# USB.net
KiCad netlist of a schematic drawn in Altium Designer
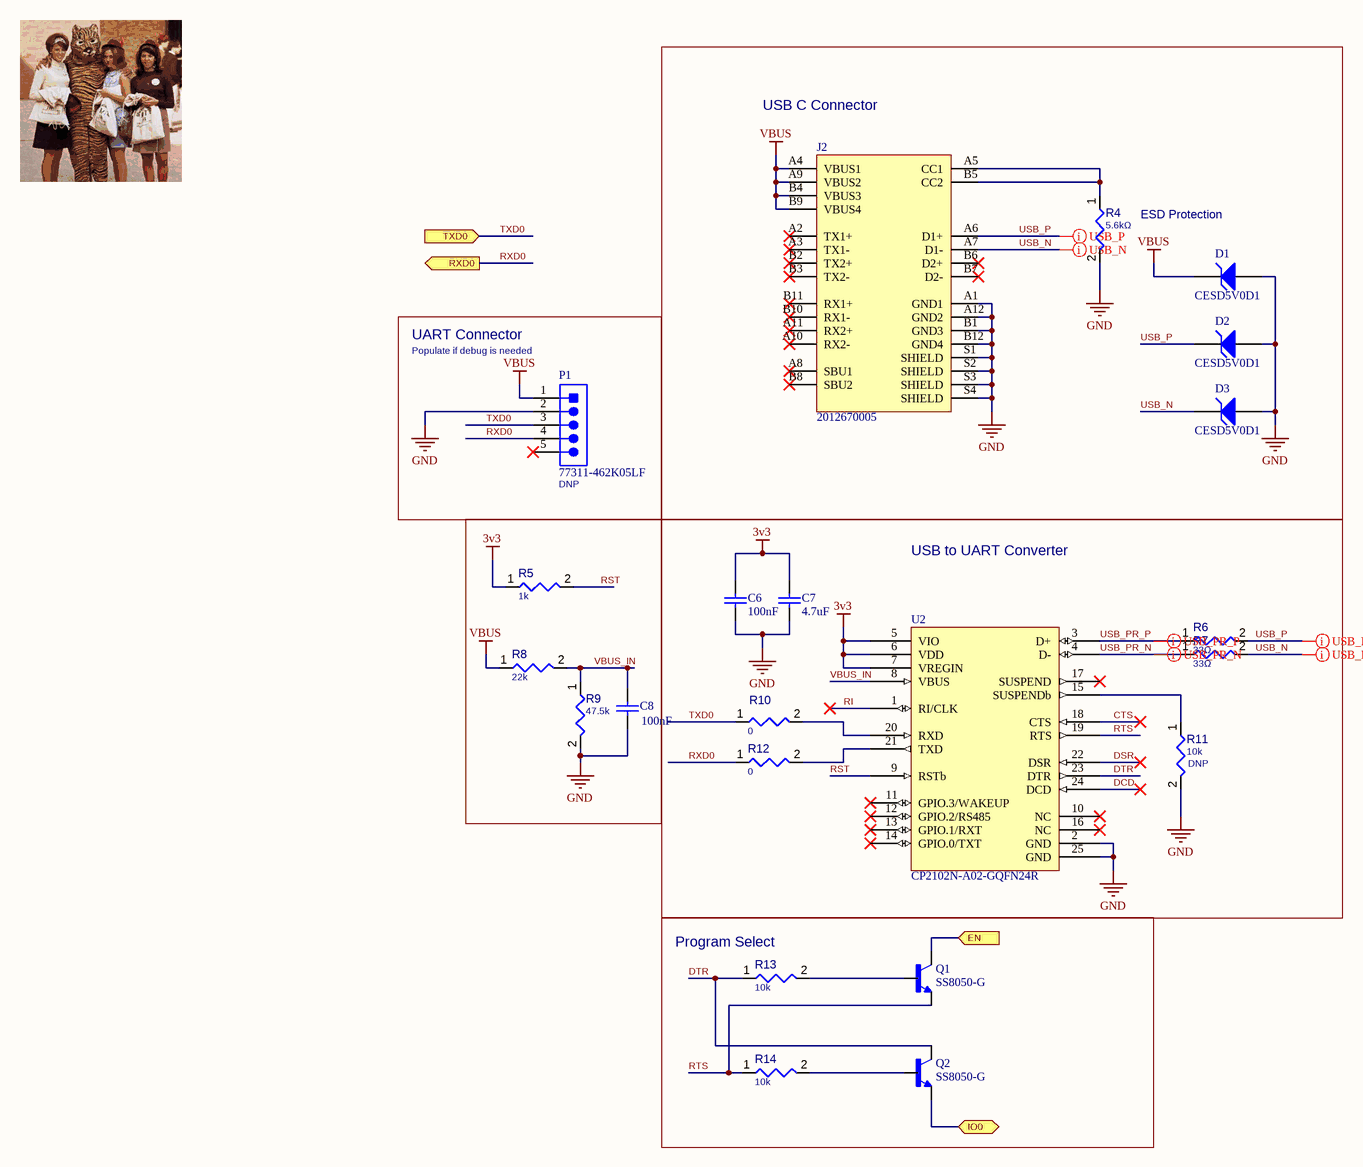
[diagram p0: USB.SchDoc]

(export (version "E")
  (design (tool "Eeschema 10.0.6"))
  (components
    (comp (ref "C6")
      (value "GRM155R71E104KE14D")
      (footprint "Capacitor_0402")
      (description "Chip Capacitor 100nF 0402 25V X7R")
      (fields (field (name "CAPACITANCE") "100nF"))
      (libsource (lib "RIT Launch Initiative") (part "CAPACITOR"))
    )
    (comp (ref "C7")
      (value "GRM155R60J475ME87D")
      (footprint "Capacitor_0402")
      (description "6.3V 4.7uF X5R ±20% 0402 Multilayer Ceramic Capacitors MLCC - SMD/SMT ROHS")
      (fields
        (field (name "CAPACITANCE") "4.7uF")
        (field (name "TOLERANCE") "20%")
        (field (name "JLCPCB PART #") "C23733")
      )
      (libsource (lib "RIT Launch Initiative") (part "CAPACITOR"))
    )
    (comp (ref "C8")
      (value "GRM155R71E104KE14D")
      (footprint "Capacitor_0402")
      (description "Chip Capacitor 100nF 0402 25V X7R")
      (fields (field (name "CAPACITANCE") "100nF"))
      (libsource (lib "RIT Launch Initiative") (part "CAPACITOR"))
    )
    (comp (ref "D1")
      (value "CESD5V0D1")
      (footprint "JSCJ-SOD-123-2_V")
      (description "Uni-driection ESD Protection Diode, 5 V, 1 uA, 2-Pin SOD-123, RoHS, Tape and Reel")
      (fields
        (field (name "MANUFACTURER") "Jiangsu Changjiang Electronics Technology")
        (field (name "JLCPCB PART #") "C85649")
      )
      (libsource (lib "RIT Launch Initiative") (part "DZEN-AK-2"))
    )
    (comp (ref "D2")
      (value "CESD5V0D1")
      (footprint "JSCJ-SOD-123-2_V")
      (description "Uni-driection ESD Protection Diode, 5 V, 1 uA, 2-Pin SOD-123, RoHS, Tape and Reel")
      (fields (field (name "MANUFACTURER") "Jiangsu Changjiang Electronics Technology"))
      (libsource (lib "RIT Launch Initiative") (part "DZEN-AK-2"))
    )
    (comp (ref "D3")
      (value "CESD5V0D1")
      (footprint "JSCJ-SOD-123-2_V")
      (description "Uni-driection ESD Protection Diode, 5 V, 1 uA, 2-Pin SOD-123, RoHS, Tape and Reel")
      (fields (field (name "MANUFACTURER") "Jiangsu Changjiang Electronics Technology"))
      (libsource (lib "RIT Launch Initiative") (part "DZEN-AK-2"))
    )
    (comp (ref "J2")
      (value "2012670005")
      (footprint "2012670005-Footprint-1")
      (description "Conn USB 3.1 Type C F 24 POS 0.5mm Solder RA SMD 24 Terminal 1 Port T/R")
      (fields (field (name "JLCPCB PART #") "C565324"))
      (libsource (lib "RIT Launch Initiative") (part "2012670005"))
    )
    (comp (ref "P1")
      (value "77311-462K05LF")
      (footprint "FCI-77311-5_V")
      (fields (field (name "MANUFACTURER") "FCI Electronics") (field (name "DNP") "DNP"))
      (libsource (lib "RIT Launch Initiative") (part "CN-1P-M-R5"))
    )
    (comp (ref "Q1")
      (value "SS8050-G")
      (footprint "SS8050-G-Footprint-1")
      (description "Trans Gp Bjt NPN 25V 1.5A 300MW 3-PIN SOT-23 T/r")
      (fields (field (name "JLCPCB PART #") "C2150"))
      (libsource (lib "RIT Launch Initiative") (part "SS8050-G-Symbol-1"))
    )
    (comp (ref "Q2")
      (value "SS8050-G")
      (footprint "SS8050-G-Footprint-1")
      (description "Trans Gp Bjt NPN 25V 1.5A 300MW 3-PIN SOT-23 T/r")
      (libsource (lib "RIT Launch Initiative") (part "SS8050-G-Symbol-1"))
    )
    (comp (ref "R4")
      (value "5.6kΩ")
      (footprint "RESC0402(1005)_L")
      (description "5K6 0.063W 5% 0402 (1005 Metric)  SMD")
      (fields (field (name "TOLERANCE") "5%") (field (name "POWER") "63mW"))
      (libsource (lib "RIT Launch Initiative") (part "5D6KR2J"))
    )
    (comp (ref "R5")
      (value "1k")
      (footprint "RESC0402(1005)_L")
      (description "Chip Resistor, 1 kOhms, +/-5 %, 63 mW, -55 to 155 degC, 0402")
      (fields (field (name "POWER") "63mW") (field (name "TOLERANCE") "5%"))
      (libsource (lib "RIT Launch Initiative") (part "RES-2"))
    )
    (comp (ref "R6")
      (value "33Ω")
      (footprint "RESC0402(1005)_L")
      (description "33R 0.063W 5% 0402 (1005 Metric)  SMD")
      (fields (field (name "TOLERANCE") "5%") (field (name "POWER") "63mW"))
      (libsource (lib "RIT Launch Initiative") (part "33R2J"))
    )
    (comp (ref "R7")
      (value "33Ω")
      (footprint "RESC0402(1005)_L")
      (description "33R 0.063W 5% 0402 (1005 Metric)  SMD")
      (fields (field (name "TOLERANCE") "5%") (field (name "POWER") "63mW"))
      (libsource (lib "RIT Launch Initiative") (part "33R2J"))
    )
    (comp (ref "R8")
      (value "22k")
      (footprint "RESC0402(1005)_L")
      (description "Chip Resistor, 22 kOhms, +/-1 %, 63 mW, -55 to 155 degC, 0402")
      (fields (field (name "POWER") "63mW") (field (name "TOLERANCE") "1%"))
      (libsource (lib "RIT Launch Initiative") (part "RES-2"))
    )
    (comp (ref "R9")
      (value "47.5k")
      (footprint "RESC0402(1005)_L")
      (description "Chip Resistor, 47,5 kOhms, +/-1 %, 63 mW, -55 to 155 degC, 0402")
      (fields (field (name "TOLERANCE") "1%") (field (name "POWER") "63mW"))
      (libsource (lib "RIT Launch Initiative") (part "RES-2"))
    )
    (comp (ref "R10")
      (value "0")
      (footprint "RESC0402(1005)_L")
      (description "Jumper 0402")
      (fields (field (name "JLCPCB PART #") "C17168"))
      (libsource (lib "RIT Launch Initiative") (part "RES-2"))
    )
    (comp (ref "R11")
      (value "10k")
      (footprint "RESC0402(1005)_L")
      (description "Chip Resistor, 10 kOhms, +/-1 %, 63 mW, -55 to 125 degC, 0402")
      (fields (field (name "POWER") "63mW") (field (name "TOLERANCE") "1%") (field (name "DNP") "DNP"))
      (libsource (lib "RIT Launch Initiative") (part "RES-2"))
    )
    (comp (ref "R12")
      (value "0")
      (footprint "RESC0402(1005)_L")
      (description "Jumper 0402")
      (libsource (lib "RIT Launch Initiative") (part "RES-2"))
    )
    (comp (ref "R13")
      (value "10k")
      (footprint "RESC0402(1005)_L")
      (description "Chip Resistor, 10 kOhms, +/-1 %, 63 mW, -55 to 125 degC, 0402")
      (fields (field (name "POWER") "63mW") (field (name "TOLERANCE") "1%"))
      (libsource (lib "RIT Launch Initiative") (part "RES-2"))
    )
    (comp (ref "R14")
      (value "10k")
      (footprint "RESC0402(1005)_L")
      (description "Chip Resistor, 10 kOhms, +/-1 %, 63 mW, -55 to 125 degC, 0402")
      (fields (field (name "POWER") "63mW") (field (name "TOLERANCE") "1%"))
      (libsource (lib "RIT Launch Initiative") (part "RES-2"))
    )
    (comp (ref "U2")
      (value "CP2102N-A02-GQFN24R")
      (footprint "CP2102N-A02-GQFN24R-Footprint-1")
      (description "Full Speed USB to UART Bridge USB 2.0 3.3V T/R Automotive 24-Pin QFN EP")
      (libsource (lib "RIT Launch Initiative") (part "CP2102N-A02-GQFN24R"))
    )
  )
  (nets
    (net (code "1") (name "/CTS") (class "Default")
      (node (ref "U2") (pin "18") (pinfunction "CTS_18") (pintype "input+no_connect"))
    )
    (net (code "2") (name "/DCD") (class "Default")
      (node (ref "U2") (pin "24") (pinfunction "DCD_24") (pintype "input+no_connect"))
    )
    (net (code "3") (name "/DSR") (class "Default")
      (node (ref "U2") (pin "22") (pinfunction "DSR_22") (pintype "input+no_connect"))
    )
    (net (code "4") (name "/DTR") (class "Default")
      (node (ref "Q2") (pin "3") (pinfunction "C_3") (pintype "passive"))
      (node (ref "R13") (pin "1") (pinfunction "1_1") (pintype "passive"))
      (node (ref "U2") (pin "23") (pinfunction "DTR_23") (pintype "output"))
    )
    (net (code "5") (name "/EN") (class "Default")
      (node (ref "Q1") (pin "3") (pinfunction "C_3") (pintype "passive"))
    )
    (net (code "6") (name "/IO0") (class "Default")
      (node (ref "Q2") (pin "2") (pinfunction "E_2") (pintype "passive"))
    )
    (net (code "7") (name "/RI") (class "Default")
      (node (ref "U2") (pin "1") (pinfunction "RI/CLK_1") (pintype "bidirectional+no_connect"))
    )
    (net (code "8") (name "/RST") (class "Default")
      (node (ref "R5") (pin "2") (pinfunction "2_2") (pintype "passive"))
      (node (ref "U2") (pin "9") (pinfunction "RSTb_9") (pintype "input"))
    )
    (net (code "9") (name "/RTS") (class "Default")
      (node (ref "Q1") (pin "2") (pinfunction "E_2") (pintype "passive"))
      (node (ref "R14") (pin "1") (pinfunction "1_1") (pintype "passive"))
      (node (ref "U2") (pin "19") (pinfunction "RTS_19") (pintype "output"))
    )
    (net (code "10") (name "/RXD0") (class "Default")
      (node (ref "P1") (pin "4") (pinfunction "VCC_4") (pintype "passive"))
      (node (ref "R12") (pin "1") (pinfunction "1_1") (pintype "passive"))
    )
    (net (code "11") (name "/TXD0") (class "Default")
      (node (ref "P1") (pin "3") (pinfunction "TXO_3") (pintype "passive"))
      (node (ref "R10") (pin "1") (pinfunction "1_1") (pintype "passive"))
    )
    (net (code "12") (name "/USB_N") (class "Default")
      (node (ref "D3") (pin "2") (pinfunction "K_2") (pintype "passive"))
      (node (ref "J2") (pin "A7") (pinfunction "D1-_A7") (pintype "passive"))
      (node (ref "R7") (pin "2") (pinfunction "2_2") (pintype "passive"))
    )
    (net (code "13") (name "/USB_P") (class "Default")
      (node (ref "D2") (pin "2") (pinfunction "K_2") (pintype "passive"))
      (node (ref "J2") (pin "A6") (pinfunction "D1+_A6") (pintype "passive"))
      (node (ref "R6") (pin "2") (pinfunction "2_2") (pintype "passive"))
    )
    (net (code "14") (name "/USB_PR_N") (class "Default")
      (node (ref "R7") (pin "1") (pinfunction "1_1") (pintype "passive"))
      (node (ref "U2") (pin "4") (pinfunction "D-_4") (pintype "bidirectional"))
    )
    (net (code "15") (name "/USB_PR_P") (class "Default")
      (node (ref "R6") (pin "1") (pinfunction "1_1") (pintype "passive"))
      (node (ref "U2") (pin "3") (pinfunction "D+_3") (pintype "bidirectional"))
    )
    (net (code "16") (name "/VBUS_IN") (class "Default")
      (node (ref "C8") (pin "2") (pinfunction "2_2") (pintype "passive"))
      (node (ref "R8") (pin "2") (pinfunction "2_2") (pintype "passive"))
      (node (ref "R9") (pin "1") (pinfunction "1_1") (pintype "passive"))
      (node (ref "U2") (pin "8") (pinfunction "VBUS_8") (pintype "input"))
    )
    (net (code "17") (name "3v3") (class "Default")
      (node (ref "C6") (pin "2") (pinfunction "2_2") (pintype "passive"))
      (node (ref "C7") (pin "2") (pinfunction "2_2") (pintype "passive"))
      (node (ref "R5") (pin "1") (pinfunction "1_1") (pintype "passive"))
      (node (ref "U2") (pin "5") (pinfunction "VIO_5") (pintype "power_in"))
      (node (ref "U2") (pin "6") (pinfunction "VDD_6") (pintype "power_in"))
      (node (ref "U2") (pin "7") (pinfunction "VREGIN_7") (pintype "power_in"))
    )
    (net (code "18") (name "GND") (class "Default")
      (node (ref "C6") (pin "1") (pinfunction "1_1") (pintype "passive"))
      (node (ref "C7") (pin "1") (pinfunction "1_1") (pintype "passive"))
      (node (ref "C8") (pin "1") (pinfunction "1_1") (pintype "passive"))
      (node (ref "D1") (pin "1") (pinfunction "A_1") (pintype "passive"))
      (node (ref "D2") (pin "1") (pinfunction "A_1") (pintype "passive"))
      (node (ref "D3") (pin "1") (pinfunction "A_1") (pintype "passive"))
      (node (ref "J2") (pin "A1") (pinfunction "GND1_A1") (pintype "power_in"))
      (node (ref "J2") (pin "A12") (pinfunction "GND2_A12") (pintype "power_in"))
      (node (ref "J2") (pin "B1") (pinfunction "GND3_B1") (pintype "power_in"))
      (node (ref "J2") (pin "B12") (pinfunction "GND4_B12") (pintype "power_in"))
      (node (ref "J2") (pin "S1") (pinfunction "SHIELD_S1") (pintype "power_in"))
      (node (ref "J2") (pin "S2") (pinfunction "SHIELD_S2") (pintype "power_in"))
      (node (ref "J2") (pin "S3") (pinfunction "SHIELD_S3") (pintype "power_in"))
      (node (ref "J2") (pin "S4") (pinfunction "SHIELD_S4") (pintype "power_in"))
      (node (ref "P1") (pin "2") (pinfunction "RXI_2") (pintype "passive"))
      (node (ref "R11") (pin "2") (pinfunction "2_2") (pintype "passive"))
      (node (ref "R4") (pin "2") (pinfunction "2_2") (pintype "passive"))
      (node (ref "R9") (pin "2") (pinfunction "2_2") (pintype "passive"))
      (node (ref "U2") (pin "2") (pinfunction "GND_2") (pintype "power_in"))
      (node (ref "U2") (pin "25") (pinfunction "GND_25") (pintype "power_in"))
    )
    (net (code "19") (name "Net-(J2-CC1)") (class "Default")
      (node (ref "J2") (pin "A5") (pinfunction "CC1_A5") (pintype "passive"))
      (node (ref "J2") (pin "B5") (pinfunction "CC2_B5") (pintype "passive"))
      (node (ref "R4") (pin "1") (pinfunction "1_1") (pintype "passive"))
    )
    (net (code "20") (name "Net-(Q1-B)") (class "Default")
      (node (ref "Q1") (pin "1") (pinfunction "B_1") (pintype "passive"))
      (node (ref "R13") (pin "2") (pinfunction "2_2") (pintype "passive"))
    )
    (net (code "21") (name "Net-(Q2-B)") (class "Default")
      (node (ref "Q2") (pin "1") (pinfunction "B_1") (pintype "passive"))
      (node (ref "R14") (pin "2") (pinfunction "2_2") (pintype "passive"))
    )
    (net (code "22") (name "Net-(U2-RXD)") (class "Default")
      (node (ref "R10") (pin "2") (pinfunction "2_2") (pintype "passive"))
      (node (ref "U2") (pin "20") (pinfunction "RXD_20") (pintype "input"))
    )
    (net (code "23") (name "Net-(U2-SUSPENDb)") (class "Default")
      (node (ref "R11") (pin "1") (pinfunction "1_1") (pintype "passive"))
      (node (ref "U2") (pin "15") (pinfunction "SUSPENDb_15") (pintype "output"))
    )
    (net (code "24") (name "Net-(U2-TXD)") (class "Default")
      (node (ref "R12") (pin "2") (pinfunction "2_2") (pintype "passive"))
      (node (ref "U2") (pin "21") (pinfunction "TXD_21") (pintype "output"))
    )
    (net (code "25") (name "VBUS") (class "Default")
      (node (ref "D1") (pin "2") (pinfunction "K_2") (pintype "passive"))
      (node (ref "J2") (pin "A4") (pinfunction "VBUS1_A4") (pintype "power_in"))
      (node (ref "J2") (pin "A9") (pinfunction "VBUS2_A9") (pintype "power_in"))
      (node (ref "J2") (pin "B4") (pinfunction "VBUS3_B4") (pintype "power_in"))
      (node (ref "J2") (pin "B9") (pinfunction "VBUS4_B9") (pintype "power_in"))
      (node (ref "P1") (pin "1") (pinfunction "DTR_1") (pintype "passive"))
      (node (ref "R8") (pin "1") (pinfunction "1_1") (pintype "passive"))
    )
    (net (code "26") (name "unconnected-(J2-D2+-PadB6)") (class "Default")
      (node (ref "J2") (pin "B6") (pinfunction "D2+_B6") (pintype "passive+no_connect"))
    )
    (net (code "27") (name "unconnected-(J2-D2--PadB7)") (class "Default")
      (node (ref "J2") (pin "B7") (pinfunction "D2-_B7") (pintype "passive+no_connect"))
    )
    (net (code "28") (name "unconnected-(J2-RX1+-PadB11)") (class "Default")
      (node (ref "J2") (pin "B11") (pinfunction "RX1+_B11") (pintype "passive+no_connect"))
    )
    (net (code "29") (name "unconnected-(J2-RX1--PadB10)") (class "Default")
      (node (ref "J2") (pin "B10") (pinfunction "RX1-_B10") (pintype "passive+no_connect"))
    )
    (net (code "30") (name "unconnected-(J2-RX2+-PadA11)") (class "Default")
      (node (ref "J2") (pin "A11") (pinfunction "RX2+_A11") (pintype "passive+no_connect"))
    )
    (net (code "31") (name "unconnected-(J2-RX2--PadA10)") (class "Default")
      (node (ref "J2") (pin "A10") (pinfunction "RX2-_A10") (pintype "passive+no_connect"))
    )
    (net (code "32") (name "unconnected-(J2-SBU1-PadA8)") (class "Default")
      (node (ref "J2") (pin "A8") (pinfunction "SBU1_A8") (pintype "passive+no_connect"))
    )
    (net (code "33") (name "unconnected-(J2-SBU2-PadB8)") (class "Default")
      (node (ref "J2") (pin "B8") (pinfunction "SBU2_B8") (pintype "passive+no_connect"))
    )
    (net (code "34") (name "unconnected-(J2-TX1+-PadA2)") (class "Default")
      (node (ref "J2") (pin "A2") (pinfunction "TX1+_A2") (pintype "passive+no_connect"))
    )
    (net (code "35") (name "unconnected-(J2-TX1--PadA3)") (class "Default")
      (node (ref "J2") (pin "A3") (pinfunction "TX1-_A3") (pintype "passive+no_connect"))
    )
    (net (code "36") (name "unconnected-(J2-TX2+-PadB2)") (class "Default")
      (node (ref "J2") (pin "B2") (pinfunction "TX2+_B2") (pintype "passive+no_connect"))
    )
    (net (code "37") (name "unconnected-(J2-TX2--PadB3)") (class "Default")
      (node (ref "J2") (pin "B3") (pinfunction "TX2-_B3") (pintype "passive+no_connect"))
    )
    (net (code "38") (name "unconnected-(P1-CTS-Pad5)") (class "Default")
      (node (ref "P1") (pin "5") (pinfunction "CTS_5") (pintype "passive+no_connect"))
    )
    (net (code "39") (name "unconnected-(U2-GPIO.0{slash}TXT-Pad14)") (class "Default")
      (node (ref "U2") (pin "14") (pinfunction "GPIO.0/TXT_14") (pintype "bidirectional+no_connect"))
    )
    (net (code "40") (name "unconnected-(U2-GPIO.1{slash}RXT-Pad13)") (class "Default")
      (node (ref "U2") (pin "13") (pinfunction "GPIO.1/RXT_13") (pintype "bidirectional+no_connect"))
    )
    (net (code "41") (name "unconnected-(U2-GPIO.2{slash}RS485-Pad12)") (class "Default")
      (node (ref "U2") (pin "12") (pinfunction "GPIO.2/RS485_12") (pintype "bidirectional+no_connect"))
    )
    (net (code "42") (name "unconnected-(U2-GPIO.3{slash}WAKEUP-Pad11)") (class "Default")
      (node (ref "U2") (pin "11") (pinfunction "GPIO.3/WAKEUP_11") (pintype "bidirectional+no_connect"))
    )
    (net (code "43") (name "unconnected-(U2-NC-Pad10)") (class "Default")
      (node (ref "U2") (pin "10") (pinfunction "NC_10") (pintype "open_emitter+no_connect"))
    )
    (net (code "44") (name "unconnected-(U2-NC-Pad16)") (class "Default")
      (node (ref "U2") (pin "16") (pinfunction "NC_16") (pintype "open_emitter+no_connect"))
    )
    (net (code "45") (name "unconnected-(U2-SUSPEND-Pad17)") (class "Default")
      (node (ref "U2") (pin "17") (pinfunction "SUSPEND_17") (pintype "output+no_connect"))
    )
  )
)
